# mcu_valdis3.net
KiCad netlist of a schematic drawn in Altium Designer
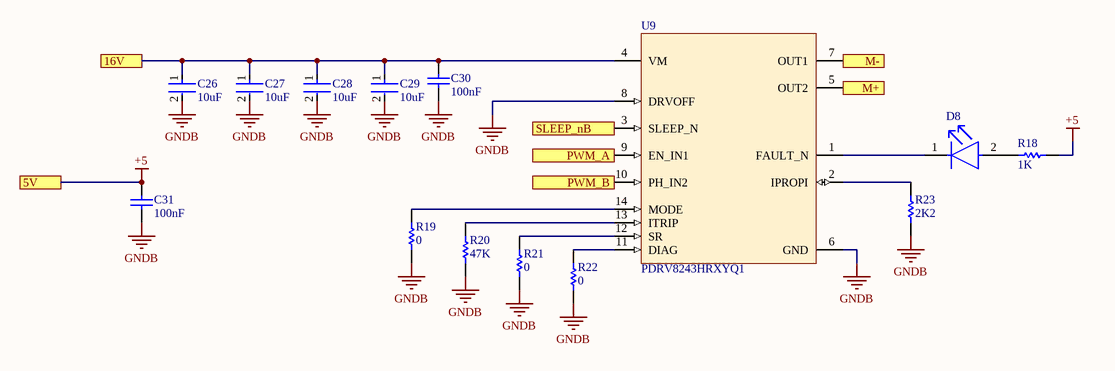
[diagram p0: mcu_valdis3.SchDoc]

(export (version "E")
  (design (tool "Eeschema 10.0.6"))
  (components
    (comp (ref "C26")
      (value "10uF")
      (footprint "FP-CL21-IPC_C")
      (description "CL21 Series 0805 22uF 25V ±20% Tolerance X5R Multilayer Ceramic Chip Capacitor")
      (libsource (lib "Altium Content Vault") (part "b4654b650e69147ec39a6b967a45e02"))
    )
    (comp (ref "C27")
      (value "10uF")
      (footprint "FP-CL21-IPC_C")
      (description "CL21 Series 0805 22uF 25V ±20% Tolerance X5R Multilayer Ceramic Chip Capacitor")
      (libsource (lib "Altium Content Vault") (part "b4654b650e69147ec39a6b967a45e02"))
    )
    (comp (ref "C28")
      (value "10uF")
      (footprint "FP-CL21-IPC_C")
      (description "CL21 Series 0805 22uF 25V ±20% Tolerance X5R Multilayer Ceramic Chip Capacitor")
      (libsource (lib "Altium Content Vault") (part "b4654b650e69147ec39a6b967a45e02"))
    )
    (comp (ref "C29")
      (value "10uF")
      (footprint "FP-CL21-IPC_C")
      (description "CL21 Series 0805 22uF 25V ±20% Tolerance X5R Multilayer Ceramic Chip Capacitor")
      (libsource (lib "Altium Content Vault") (part "b4654b650e69147ec39a6b967a45e02"))
    )
    (comp (ref "C30")
      (value "100nF")
      (footprint "CAPC1608X90X35ML10T15")
      (description "Chip Capacitor, 22 pF, +/- 5%, 50 V, -55 to 125 degC, 0603 (1608 Metric), RoHS, Tape and Reel")
      (fields (field (name "MANUFACTURER") "Murata"))
      (libsource (lib "Altium Content Vault") (part "CAP-NP-2"))
    )
    (comp (ref "C31")
      (value "100nF")
      (footprint "CAPC1608X90X35ML10T15")
      (description "Chip Capacitor, 22 pF, +/- 5%, 50 V, -55 to 125 degC, 0603 (1608 Metric), RoHS, Tape and Reel")
      (fields (field (name "MANUFACTURER") "Murata"))
      (libsource (lib "Altium Content Vault") (part "CAP-NP-2"))
    )
    (comp (ref "D8")
      (value "LTST-C191TBKT")
      (footprint "FP-LTST-C191TBKT-MFG")
      (description "LED BLUE CLEAR CHIP SMD")
      (libsource (lib "Altium Content Vault") (part "8706943c75ba83719d021d2fdc84c58"))
    )
    (comp (ref "R18")
      (value "1K")
      (footprint "RESC1609X50X30NL8T20")
      (description "Chip Resistor, 0 Ohm, Jumper, 100 mW, -55 to 155 degC, 0603 (1608 Metric), RoHS, Tape and Reel")
      (fields (field (name "MANUFACTURER") "Vishay Semiconductor"))
      (libsource (lib "Altium Content Vault") (part "RES-2"))
    )
    (comp (ref "R19")
      (value "0")
      (footprint "RESC1609X50X30NL8T20")
      (description "Chip Resistor, 0 Ohm, Jumper, 100 mW, -55 to 155 degC, 0603 (1608 Metric), RoHS, Tape and Reel")
      (fields (field (name "MANUFACTURER") "Vishay Semiconductor"))
      (libsource (lib "Altium Content Vault") (part "RES-2"))
    )
    (comp (ref "R20")
      (value "47K")
      (footprint "RESC1609X50X30NL8T20")
      (description "Chip Resistor, 0 Ohm, Jumper, 100 mW, -55 to 155 degC, 0603 (1608 Metric), RoHS, Tape and Reel")
      (fields (field (name "MANUFACTURER") "Vishay Semiconductor"))
      (libsource (lib "Altium Content Vault") (part "RES-2"))
    )
    (comp (ref "R21")
      (value "0")
      (footprint "RESC1609X50X30NL8T20")
      (description "Chip Resistor, 0 Ohm, Jumper, 100 mW, -55 to 155 degC, 0603 (1608 Metric), RoHS, Tape and Reel")
      (fields (field (name "MANUFACTURER") "Vishay Semiconductor"))
      (libsource (lib "Altium Content Vault") (part "RES-2"))
    )
    (comp (ref "R22")
      (value "0")
      (footprint "RESC1609X50X30NL8T20")
      (description "Chip Resistor, 0 Ohm, Jumper, 100 mW, -55 to 155 degC, 0603 (1608 Metric), RoHS, Tape and Reel")
      (fields (field (name "MANUFACTURER") "Vishay Semiconductor"))
      (libsource (lib "Altium Content Vault") (part "RES-2"))
    )
    (comp (ref "R23")
      (value "2K2")
      (footprint "RESC1609X50X30NL8T20")
      (description "Chip Resistor, 0 Ohm, Jumper, 100 mW, -55 to 155 degC, 0603 (1608 Metric), RoHS, Tape and Reel")
      (fields (field (name "MANUFACTURER") "Vishay Semiconductor"))
      (libsource (lib "Altium Content Vault") (part "RES-2"))
    )
    (comp (ref "U9")
      (value "PDRV8243HRXYQ1")
      (footprint "RXY0014A-MFG")
      (description "No Description Available")
      (fields (field (name "COPYRIGHT") "Copyright (C) 2022 Ultra Librarian. All rights reserved."))
      (libsource (lib "Valdis_Components") (part "PDRV8243HRXYQ1"))
    )
  )
  (nets
    (net (code "1") (name "+5") (class "Default")
      (node (ref "C31") (pin "2") (pinfunction "2_2") (pintype "passive"))
      (node (ref "R18") (pin "2") (pinfunction "2_2") (pintype "passive"))
    )
    (net (code "2") (name "/16V") (class "Default")
      (node (ref "C26") (pin "1") (pinfunction "1_1") (pintype "passive"))
      (node (ref "C27") (pin "1") (pinfunction "1_1") (pintype "passive"))
      (node (ref "C28") (pin "1") (pinfunction "1_1") (pintype "passive"))
      (node (ref "C29") (pin "1") (pinfunction "1_1") (pintype "passive"))
      (node (ref "C30") (pin "2") (pinfunction "2_2") (pintype "passive"))
      (node (ref "U9") (pin "4") (pinfunction "VM_4") (pintype "power_in"))
    )
    (net (code "3") (name "/M+") (class "Default")
      (node (ref "U9") (pin "5") (pinfunction "OUT2_5") (pintype "passive"))
    )
    (net (code "4") (name "/M-") (class "Default")
      (node (ref "U9") (pin "7") (pinfunction "OUT1_7") (pintype "passive"))
    )
    (net (code "5") (name "/PWM_A") (class "Default")
      (node (ref "U9") (pin "9") (pinfunction "EN_IN1_9") (pintype "input"))
    )
    (net (code "6") (name "/PWM_B") (class "Default")
      (node (ref "U9") (pin "10") (pinfunction "PH_IN2_10") (pintype "input"))
    )
    (net (code "7") (name "/SLEEP_nB") (class "Default")
      (node (ref "U9") (pin "3") (pinfunction "SLEEP_N_3") (pintype "input"))
    )
    (net (code "8") (name "GNDB") (class "Default")
      (node (ref "C26") (pin "2") (pinfunction "2_2") (pintype "passive"))
      (node (ref "C27") (pin "2") (pinfunction "2_2") (pintype "passive"))
      (node (ref "C28") (pin "2") (pinfunction "2_2") (pintype "passive"))
      (node (ref "C29") (pin "2") (pinfunction "2_2") (pintype "passive"))
      (node (ref "C30") (pin "1") (pinfunction "1_1") (pintype "passive"))
      (node (ref "C31") (pin "1") (pinfunction "1_1") (pintype "passive"))
      (node (ref "R19") (pin "1") (pinfunction "1_1") (pintype "passive"))
      (node (ref "R20") (pin "1") (pinfunction "1_1") (pintype "passive"))
      (node (ref "R21") (pin "1") (pinfunction "1_1") (pintype "passive"))
      (node (ref "R22") (pin "1") (pinfunction "1_1") (pintype "passive"))
      (node (ref "R23") (pin "1") (pinfunction "1_1") (pintype "passive"))
      (node (ref "U9") (pin "6") (pinfunction "GND_6") (pintype "power_in"))
      (node (ref "U9") (pin "8") (pinfunction "DRVOFF_8") (pintype "input"))
    )
    (net (code "9") (name "Net-(D8-A)") (class "Default")
      (node (ref "D8") (pin "2") (pinfunction "A_2") (pintype "passive"))
      (node (ref "R18") (pin "1") (pinfunction "1_1") (pintype "passive"))
    )
    (net (code "10") (name "Net-(D8-C)") (class "Default")
      (node (ref "D8") (pin "1") (pinfunction "C_1") (pintype "passive"))
      (node (ref "U9") (pin "1") (pinfunction "FAULT_N_1") (pintype "open_collector"))
    )
    (net (code "11") (name "Net-(U9-DIAG)") (class "Default")
      (node (ref "R22") (pin "2") (pinfunction "2_2") (pintype "passive"))
      (node (ref "U9") (pin "11") (pinfunction "DIAG_11") (pintype "input"))
    )
    (net (code "12") (name "Net-(U9-IPROPI)") (class "Default")
      (node (ref "R23") (pin "2") (pinfunction "2_2") (pintype "passive"))
      (node (ref "U9") (pin "2") (pinfunction "IPROPI_2") (pintype "bidirectional"))
    )
    (net (code "13") (name "Net-(U9-ITRIP)") (class "Default")
      (node (ref "R20") (pin "2") (pinfunction "2_2") (pintype "passive"))
      (node (ref "U9") (pin "13") (pinfunction "ITRIP_13") (pintype "input"))
    )
    (net (code "14") (name "Net-(U9-MODE)") (class "Default")
      (node (ref "R19") (pin "2") (pinfunction "2_2") (pintype "passive"))
      (node (ref "U9") (pin "14") (pinfunction "MODE_14") (pintype "input"))
    )
    (net (code "15") (name "Net-(U9-SR)") (class "Default")
      (node (ref "R21") (pin "2") (pinfunction "2_2") (pintype "passive"))
      (node (ref "U9") (pin "12") (pinfunction "SR_12") (pintype "input"))
    )
  )
)
